# weather-cube_wifi_controller.net
KiCad netlist of a schematic drawn in EAGLE
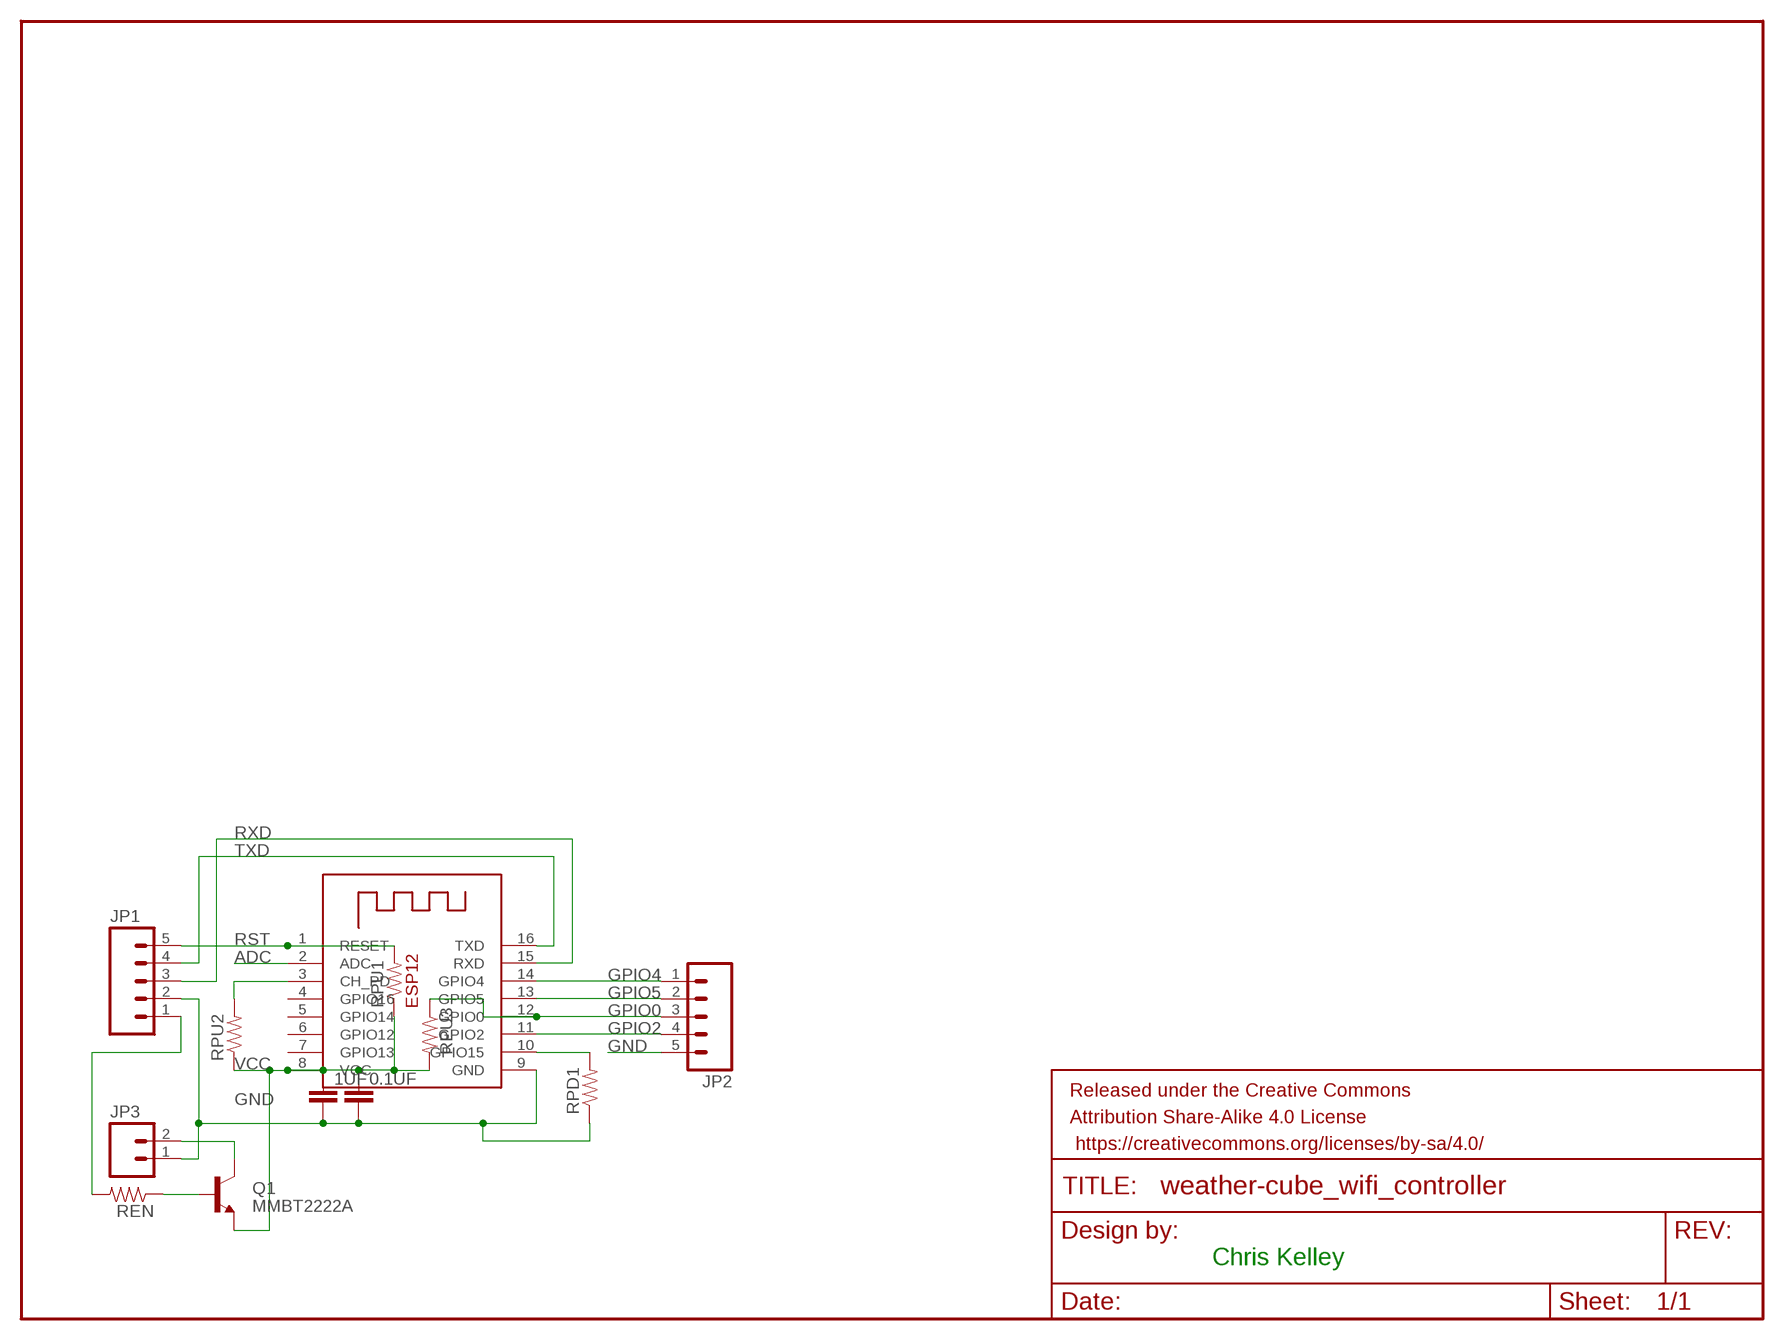
[diagram p0: schematic, sheet 1]

(export (version "E")
  (design (tool "Eeschema 10.0.6"))
  (components
    (comp (ref "0.1UF")
      (value "CAP0603-CAP")
      (footprint "eagle-import:0603-CAP")
      (libsource (lib "eagle-import") (part "CAP0603-CAP"))
    )
    (comp (ref "1UF")
      (value "CAP0603-CAP")
      (footprint "eagle-import:0603-CAP")
      (libsource (lib "eagle-import") (part "CAP0603-CAP"))
    )
    (comp (ref "FRAME1")
      (value "FRAME-LETTER")
      (footprint "eagle-import:CREATIVE_COMMONS")
      (libsource (lib "eagle-import") (part "FRAME-LETTER"))
    )
    (comp (ref "JP1")
      (value "M05PTH")
      (footprint "eagle-import:1X05")
      (libsource (lib "eagle-import") (part "M05PTH"))
    )
    (comp (ref "JP2")
      (value "M05PTH")
      (footprint "eagle-import:1X05")
      (libsource (lib "eagle-import") (part "M05PTH"))
    )
    (comp (ref "JP3")
      (value "M02PTH")
      (footprint "eagle-import:1X02")
      (libsource (lib "eagle-import") (part "M02PTH"))
    )
    (comp (ref "Q1")
      (value "MMBT2222A")
      (footprint "eagle-import:SOT23-3")
      (libsource (lib "eagle-import") (part "TRANSISTOR_NPNMMBT2222A"))
    )
    (comp (ref "REN")
      (value "RESISTOR0603-RES")
      (footprint "eagle-import:0603-RES")
      (libsource (lib "eagle-import") (part "RESISTOR0603-RES"))
    )
    (comp (ref "RPD1")
      (value "RESISTOR0603-RES")
      (footprint "eagle-import:0603-RES")
      (libsource (lib "eagle-import") (part "RESISTOR0603-RES"))
    )
    (comp (ref "RPU1")
      (value "RESISTOR0603-RES")
      (footprint "eagle-import:0603-RES")
      (libsource (lib "eagle-import") (part "RESISTOR0603-RES"))
    )
    (comp (ref "RPU2")
      (value "RESISTOR0603-RES")
      (footprint "eagle-import:0603-RES")
      (libsource (lib "eagle-import") (part "RESISTOR0603-RES"))
    )
    (comp (ref "RPU3")
      (value "RESISTOR0603-RES")
      (footprint "eagle-import:0603-RES")
      (libsource (lib "eagle-import") (part "RESISTOR0603-RES"))
    )
    (comp (ref "X1")
      (value "ESP-12")
      (footprint "eagle-import:ESP-12")
      (libsource (lib "eagle-import") (part "ESP-12"))
    )
  )
  (nets
    (net (code "1") (name "/ADC") (class "Default")
      (node (ref "X1") (pin "2") (pinfunction "ADC_2") (pintype "passive"))
    )
    (net (code "2") (name "/GND") (class "Default")
      (node (ref "0.1UF") (pin "2") (pinfunction "2_2") (pintype "passive"))
      (node (ref "1UF") (pin "2") (pinfunction "2_2") (pintype "passive"))
      (node (ref "JP1") (pin "2") (pinfunction "2_2") (pintype "passive"))
      (node (ref "JP2") (pin "5") (pinfunction "5_5") (pintype "passive"))
      (node (ref "JP3") (pin "1") (pinfunction "1_1") (pintype "passive"))
      (node (ref "RPD1") (pin "1") (pinfunction "1_1") (pintype "passive"))
      (node (ref "X1") (pin "9") (pinfunction "GND_9") (pintype "power_in"))
    )
    (net (code "3") (name "/GPIO0") (class "Default")
      (node (ref "JP2") (pin "3") (pinfunction "3_3") (pintype "passive"))
      (node (ref "RPU3") (pin "1") (pinfunction "1_1") (pintype "passive"))
      (node (ref "X1") (pin "12") (pinfunction "GPIO0_12") (pintype "bidirectional"))
    )
    (net (code "4") (name "/GPIO2") (class "Default")
      (node (ref "JP2") (pin "4") (pinfunction "4_4") (pintype "passive"))
      (node (ref "X1") (pin "11") (pinfunction "GPIO2_11") (pintype "bidirectional"))
    )
    (net (code "5") (name "/GPIO4") (class "Default")
      (node (ref "JP2") (pin "1") (pinfunction "1_1") (pintype "passive"))
      (node (ref "X1") (pin "14") (pinfunction "GPIO4_14") (pintype "bidirectional"))
    )
    (net (code "6") (name "/GPIO5") (class "Default")
      (node (ref "JP2") (pin "2") (pinfunction "2_2") (pintype "passive"))
      (node (ref "X1") (pin "13") (pinfunction "GPIO5_13") (pintype "bidirectional"))
    )
    (net (code "7") (name "/RST") (class "Default")
      (node (ref "JP1") (pin "5") (pinfunction "5_5") (pintype "passive"))
      (node (ref "RPU1") (pin "2") (pinfunction "2_2") (pintype "passive"))
      (node (ref "X1") (pin "1") (pinfunction "RESET_1") (pintype "input"))
    )
    (net (code "8") (name "/RXD") (class "Default")
      (node (ref "JP1") (pin "3") (pinfunction "3_3") (pintype "passive"))
      (node (ref "X1") (pin "15") (pinfunction "RXD_15") (pintype "input"))
    )
    (net (code "9") (name "/TXD") (class "Default")
      (node (ref "JP1") (pin "4") (pinfunction "4_4") (pintype "passive"))
      (node (ref "X1") (pin "16") (pinfunction "TXD_16") (pintype "output"))
    )
    (net (code "10") (name "/VCC") (class "Default")
      (node (ref "0.1UF") (pin "1") (pinfunction "1_1") (pintype "passive"))
      (node (ref "1UF") (pin "1") (pinfunction "1_1") (pintype "passive"))
      (node (ref "Q1") (pin "2") (pinfunction "E_2") (pintype "passive"))
      (node (ref "RPU1") (pin "1") (pinfunction "1_1") (pintype "passive"))
      (node (ref "RPU2") (pin "1") (pinfunction "1_1") (pintype "passive"))
      (node (ref "RPU3") (pin "2") (pinfunction "2_2") (pintype "passive"))
      (node (ref "X1") (pin "8") (pinfunction "VCC_8") (pintype "power_in"))
    )
    (net (code "11") (name "Net-(JP1-Pad1)") (class "Default")
      (node (ref "JP1") (pin "1") (pinfunction "1_1") (pintype "passive"))
      (node (ref "REN") (pin "2") (pinfunction "2_2") (pintype "passive"))
    )
    (net (code "12") (name "Net-(Q1-B)") (class "Default")
      (node (ref "Q1") (pin "1") (pinfunction "B_1") (pintype "passive"))
      (node (ref "REN") (pin "1") (pinfunction "1_1") (pintype "passive"))
    )
    (net (code "13") (name "Net-(Q1-C)") (class "Default")
      (node (ref "JP3") (pin "2") (pinfunction "2_2") (pintype "passive"))
      (node (ref "Q1") (pin "3") (pinfunction "C_3") (pintype "passive"))
    )
    (net (code "14") (name "Net-(X1-CH_PD)") (class "Default")
      (node (ref "RPU2") (pin "2") (pinfunction "2_2") (pintype "passive"))
      (node (ref "X1") (pin "3") (pinfunction "CH_PD_3") (pintype "input"))
    )
    (net (code "15") (name "Net-(X1-GPIO15)") (class "Default")
      (node (ref "RPD1") (pin "2") (pinfunction "2_2") (pintype "passive"))
      (node (ref "X1") (pin "10") (pinfunction "GPIO15_10") (pintype "bidirectional"))
    )
    (net (code "16") (name "unconnected-(X1-GPIO12-Pad6)") (class "Default")
      (node (ref "X1") (pin "6") (pinfunction "GPIO12_6") (pintype "bidirectional"))
    )
    (net (code "17") (name "unconnected-(X1-GPIO13-Pad7)") (class "Default")
      (node (ref "X1") (pin "7") (pinfunction "GPIO13_7") (pintype "bidirectional"))
    )
    (net (code "18") (name "unconnected-(X1-GPIO14-Pad5)") (class "Default")
      (node (ref "X1") (pin "5") (pinfunction "GPIO14_5") (pintype "bidirectional"))
    )
    (net (code "19") (name "unconnected-(X1-GPIO16-Pad4)") (class "Default")
      (node (ref "X1") (pin "4") (pinfunction "GPIO16_4") (pintype "bidirectional"))
    )
  )
)
